# schematic.net
KiCad netlist of a schematic drawn in Altium Designer
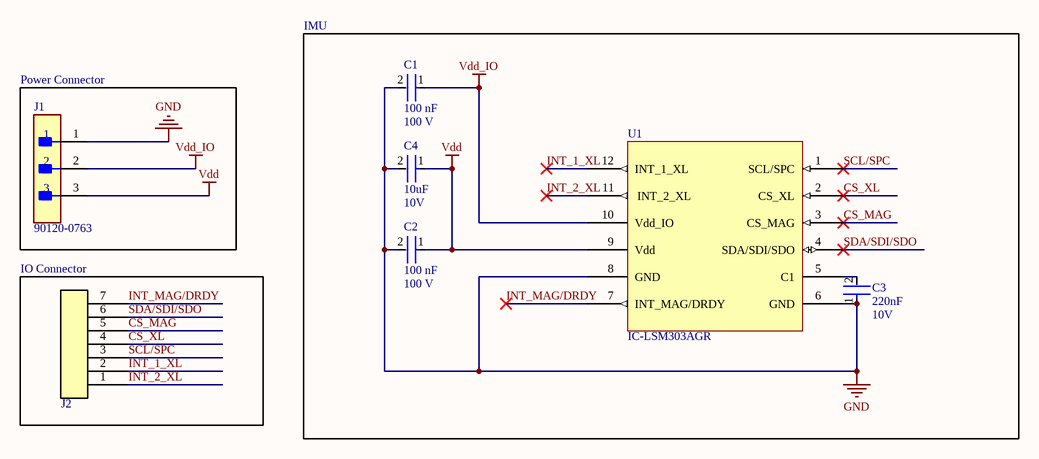
[diagram p0: schematic.SchDoc]

(export (version "E")
  (design (tool "Eeschema 10.0.6"))
  (components
    (comp (ref "C1")
      (value "CC0603KRX7R0BB104")
      (footprint "CAP-0603")
      (description "CAP CER 0.1UF 100V X7R 0603")
      (fields (field (name "CAPACITANCE") "100 nF") (field (name "VOLTAGE") "100 V"))
      (libsource (lib "JLC_25") (part "CAP-100N-0001"))
    )
    (comp (ref "C2")
      (value "CC0603KRX7R0BB104")
      (footprint "CAP-0603")
      (description "CAP CER 0.1UF 100V X7R 0603")
      (fields (field (name "CAPACITANCE") "100 nF") (field (name "VOLTAGE") "100 V"))
      (libsource (lib "JLC_25") (part "CAP-100N-0001"))
    )
    (comp (ref "C3")
      (value "CC0402KRX5R6BB224")
      (footprint "CAP-0603")
      (description "CAP CER 0.22UF 10V X5R 0603")
      (fields (field (name "CAPACITANCE") "220nF") (field (name "VOLTAGE") "10V"))
      (libsource (lib "personalparts") (part "CAP-220nF-0001"))
    )
    (comp (ref "C4")
      (value "CC0805ZKY5V6BB106")
      (footprint "CAP-0603")
      (description "CAP CER 10UF 10V Y5V 0603")
      (fields (field (name "CAPACITANCE") "10uF") (field (name "VOLTAGE") "10V"))
      (libsource (lib "personalparts") (part "CAP-10uF-0001"))
    )
    (comp (ref "J1")
      (value "90120-0763")
      (footprint "FP-90120-0763-MFG")
      (description "CONN HEADER VERT 3POS 2.54MM")
      (fields
        (field (name "MANUFACTURER") "Molex")
        (field (name "OCTOPART") "https://octopart.com/90120-0763-molex-655433")
      )
      (libsource (lib "Altium Content Vault") (part "0d3f023dd272f625e17a2be33dea85f"))
    )
    (comp (ref "J2")
      (value "61300311121")
      (footprint "CONN_PH1-07-UA_ADM")
      (description "CONN HEADER R/A 7POS 3MM")
      (libsource (lib "personalparts") (part "CONN-7POS-0001"))
    )
    (comp (ref "U1")
      (value "IC-LSM303AGR")
      (footprint "SON_03AGRTR_STM-M")
      (description "Accelerometer, Magnetometer, Temperature, 6 Axis Sensor I2C, SPI Output")
      (libsource (lib "personalparts") (part "IC-LSM303AGR"))
    )
  )
  (nets
    (net (code "1") (name "/CS_MAG") (class "Default")
      (node (ref "J2") (pin "5") (pinfunction "9_5") (pintype "passive"))
      (node (ref "U1") (pin "3") (pinfunction "CS_MAG_3") (pintype "input"))
    )
    (net (code "2") (name "/CS_XL") (class "Default")
      (node (ref "J2") (pin "4") (pinfunction "9_4") (pintype "passive"))
      (node (ref "U1") (pin "2") (pinfunction "CS_XL_2") (pintype "input"))
    )
    (net (code "3") (name "/INT_1_XL") (class "Default")
      (node (ref "J2") (pin "2") (pinfunction "8_2") (pintype "passive"))
      (node (ref "U1") (pin "12") (pinfunction "INT_1_XL_12") (pintype "output"))
    )
    (net (code "4") (name "/INT_2_XL") (class "Default")
      (node (ref "J2") (pin "1") (pinfunction "7_1") (pintype "passive"))
      (node (ref "U1") (pin "11") (pinfunction "INT_2_XL_11") (pintype "output"))
    )
    (net (code "5") (name "/INT_MAG{slash}DRDY") (class "Default")
      (node (ref "J2") (pin "7") (pinfunction "9_7") (pintype "passive"))
      (node (ref "U1") (pin "7") (pinfunction "INT_MAG/DRDY_7") (pintype "output"))
    )
    (net (code "6") (name "/SCL{slash}SPC") (class "Default")
      (node (ref "J2") (pin "3") (pinfunction "9_3") (pintype "passive"))
      (node (ref "U1") (pin "1") (pinfunction "SCL/SPC_1") (pintype "input"))
    )
    (net (code "7") (name "/SDA{slash}SDI{slash}SDO") (class "Default")
      (node (ref "J2") (pin "6") (pinfunction "9_6") (pintype "passive"))
      (node (ref "U1") (pin "4") (pinfunction "SDA/SDI/SDO_4") (pintype "bidirectional"))
    )
    (net (code "8") (name "GND") (class "Default")
      (node (ref "C1") (pin "2") (pinfunction "2_2") (pintype "passive"))
      (node (ref "C2") (pin "2") (pinfunction "2_2") (pintype "passive"))
      (node (ref "C3") (pin "1") (pinfunction "1_1") (pintype "passive"))
      (node (ref "C4") (pin "2") (pinfunction "2_2") (pintype "passive"))
      (node (ref "J1") (pin "1") (pinfunction "1_1") (pintype "passive"))
      (node (ref "U1") (pin "6") (pinfunction "GND_6") (pintype "power_in"))
      (node (ref "U1") (pin "8") (pinfunction "GND_8") (pintype "power_in"))
    )
    (net (code "9") (name "Net-(U1-C1)") (class "Default")
      (node (ref "C3") (pin "2") (pinfunction "2_2") (pintype "passive"))
      (node (ref "U1") (pin "5") (pinfunction "C1_5") (pintype "power_in"))
    )
    (net (code "10") (name "Vdd") (class "Default")
      (node (ref "C2") (pin "1") (pinfunction "1_1") (pintype "passive"))
      (node (ref "C4") (pin "1") (pinfunction "1_1") (pintype "passive"))
      (node (ref "J1") (pin "3") (pinfunction "3_3") (pintype "passive"))
      (node (ref "U1") (pin "9") (pinfunction "Vdd_9") (pintype "power_in"))
    )
    (net (code "11") (name "Vdd_IO") (class "Default")
      (node (ref "C1") (pin "1") (pinfunction "1_1") (pintype "passive"))
      (node (ref "J1") (pin "2") (pinfunction "2_2") (pintype "passive"))
      (node (ref "U1") (pin "10") (pinfunction "Vdd_IO_10") (pintype "power_in"))
    )
  )
)
